# Low_Side_Switch.net
KiCad netlist of a schematic drawn in Altium Designer
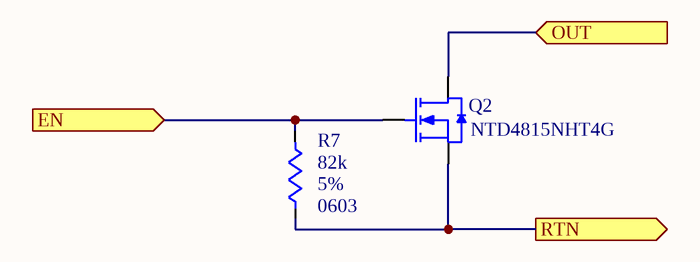
[diagram p0: Low_Side_Switch.SchDoc]

(export (version "E")
  (design (tool "Eeschema 10.0.6"))
  (components
    (comp (ref "Q2")
      (value "NFET_SOT323")
      (footprint "DPAK228P991X238-3N_NTD4815NHT4G")
      (description "MOSFET N-CH 30V 6.9A/35A DPAK")
      (fields (field (name "MANUFACTURER PART NUMBER 1") "NTD4815NHT4G"))
      (libsource (lib "discretes") (part "NFET_SOT323"))
    )
    (comp (ref "R7")
      (value "82k")
      (footprint "RESC1508X09N")
      (description "RES 82K OHM 5% 0603")
      (fields (field (name "TOLERANCE") "5%") (field (name "PACKAGE") "0603") (field (name "Comment") "RES"))
      (libsource (lib "resistors") (part "RES"))
    )
  )
  (nets
    (net (code "1") (name "/EN") (class "Default")
      (node (ref "Q2") (pin "G") (pinfunction "G_G") (pintype "passive"))
      (node (ref "R7") (pin "2") (pinfunction "2_2") (pintype "passive"))
    )
    (net (code "2") (name "/OUT") (class "Default")
      (node (ref "Q2") (pin "D") (pinfunction "D_D") (pintype "passive"))
    )
    (net (code "3") (name "/RTN") (class "Default")
      (node (ref "Q2") (pin "S") (pinfunction "S_S") (pintype "passive"))
      (node (ref "R7") (pin "1") (pinfunction "1_1") (pintype "passive"))
    )
  )
)
